# Amplifier.net
KiCad netlist of a schematic drawn in EAGLE
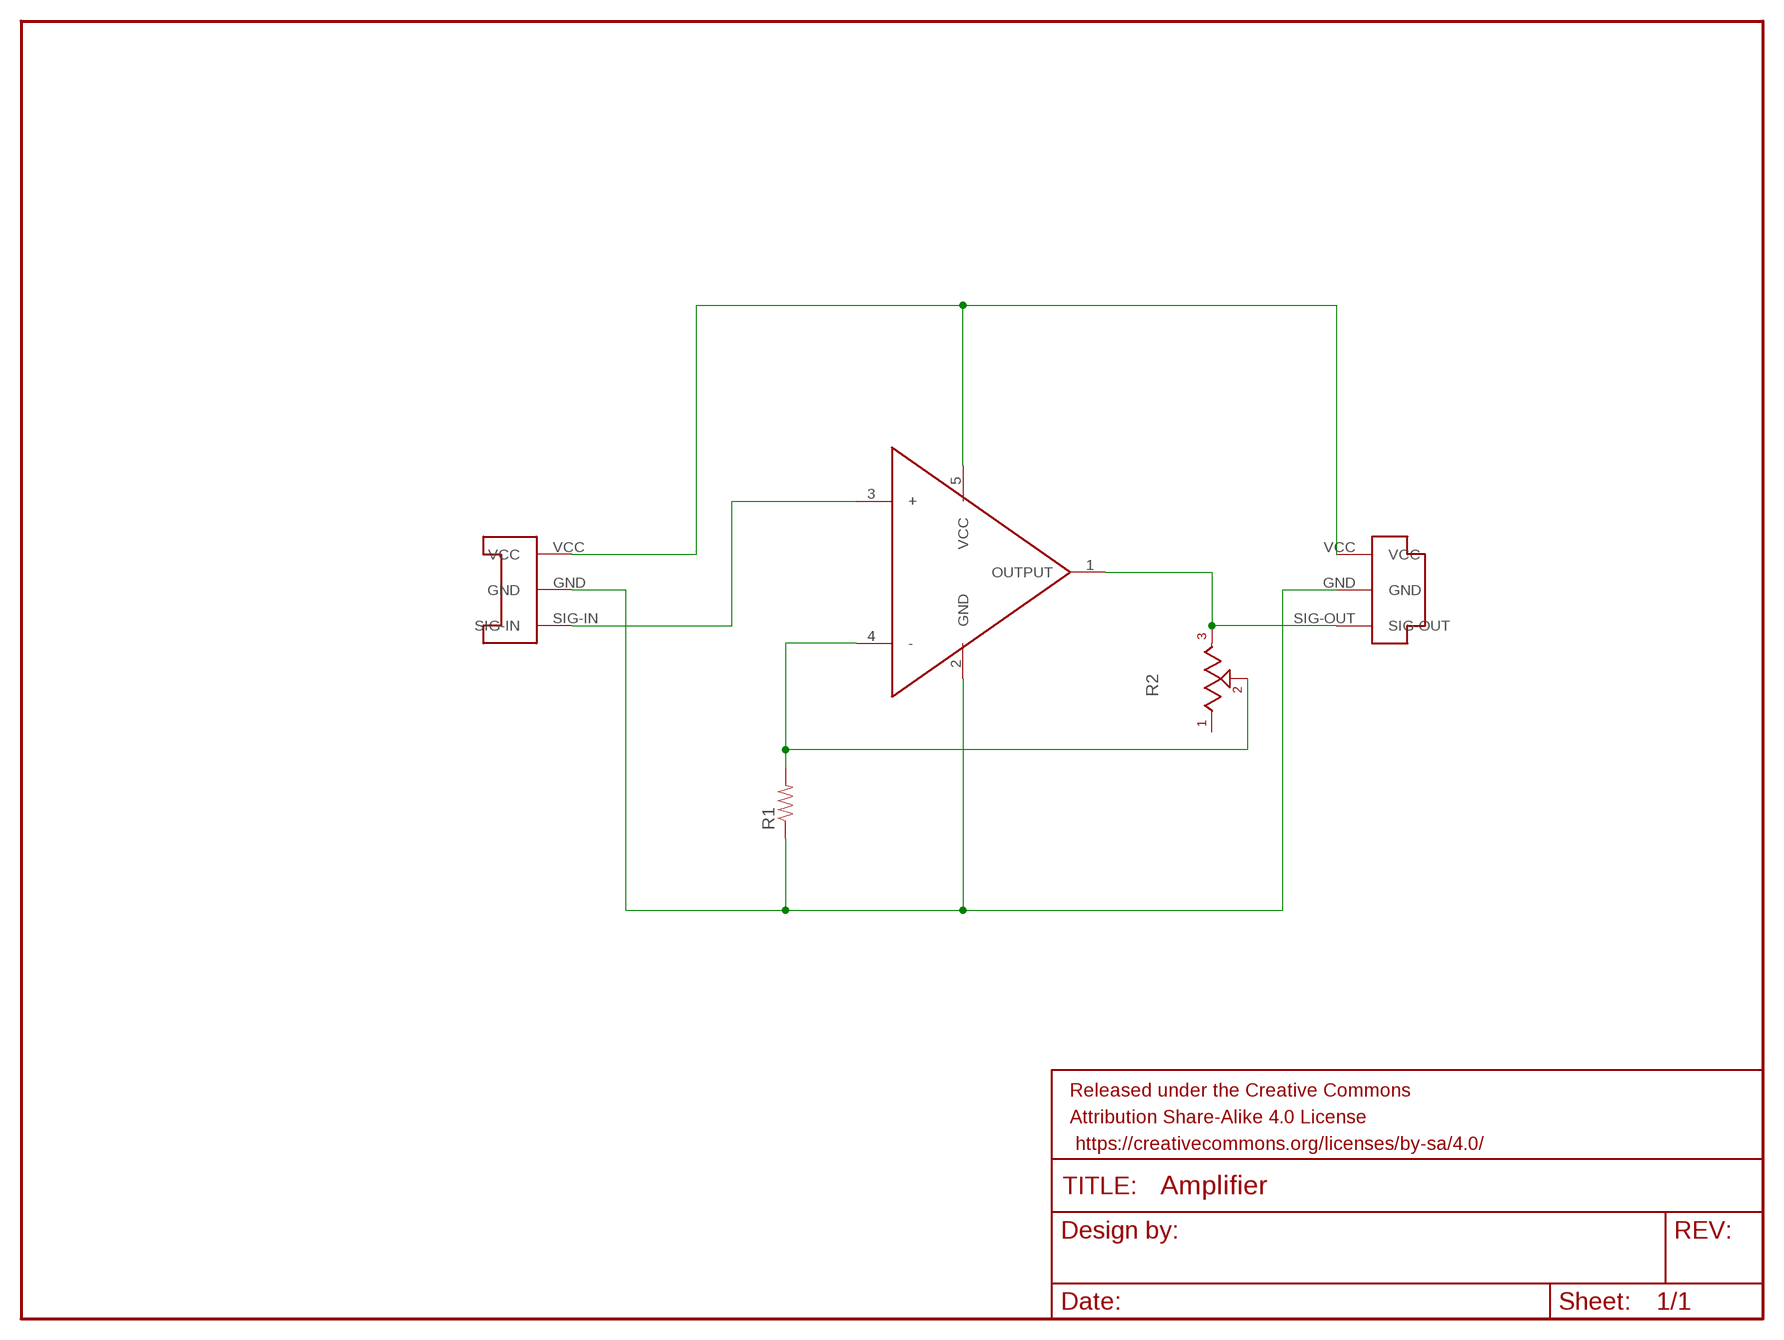
[diagram p0: schematic, sheet 1]

(export (version "E")
  (design (tool "Eeschema 10.0.6"))
  (components
    (comp (ref "FRAME1")
      (value "FRAME-LETTERNO_PACKAGE")
      (footprint "eagle-import:DUMMY")
      (fields (field (name "DESIGNER") "Nobody"))
      (libsource (lib "eagle-import") (part "FRAME-LETTERNO_PACKAGE"))
    )
    (comp (ref "R1")
      (value "RESISTOR0603")
      (footprint "eagle-import:0603-RES")
      (libsource (lib "eagle-import") (part "RESISTOR0603"))
    )
    (comp (ref "R2")
      (value "POT-TRIM-SMD-BOURNS-3314J-1")
      (footprint "eagle-import:POT-TRIM-SMD-BOURNS-3314")
      (libsource (lib "eagle-import") (part "POT-TRIM-SMD-BOURNS-3314J-1"))
    )
    (comp (ref "U$1")
      (value "CONN-PLUG-3POS-3MM")
      (footprint "eagle-import:PLUG-3POS-3MM-SMD")
      (libsource (lib "eagle-import") (part "CONN-PLUG-3POS-3MM"))
    )
    (comp (ref "U$2")
      (value "CONN-SOCKET-3POS-3MM")
      (footprint "eagle-import:SOCKET-3POS-3MM-SMD")
      (libsource (lib "eagle-import") (part "CONN-SOCKET-3POS-3MM"))
    )
    (comp (ref "U$3")
      (value "OPAMP-MCP6001SC70-5")
      (footprint "eagle-import:SC70")
      (libsource (lib "eagle-import") (part "OPAMP-MCP6001SC70-5"))
    )
  )
  (nets
    (net (code "1") (name "Net-(R2-3)") (class "Default")
      (node (ref "R2") (pin "1") (pinfunction "3_1") (pintype "passive"))
      (node (ref "U$1") (pin "SIG-OUT") (pinfunction "SIG-OUT_SIG-OUT") (pintype "bidirectional"))
      (node (ref "U$3") (pin "1") (pinfunction "OUTPUT_1") (pintype "output"))
    )
    (net (code "2") (name "Net-(U$3-+)") (class "Default")
      (node (ref "U$2") (pin "SIG-IN") (pinfunction "SIG-IN_SIG-IN") (pintype "bidirectional"))
      (node (ref "U$3") (pin "3") (pinfunction "+_3") (pintype "input"))
    )
    (net (code "3") (name "Net-(U$3--)") (class "Default")
      (node (ref "R1") (pin "2") (pinfunction "2_2") (pintype "passive"))
      (node (ref "R2") (pin "2") (pinfunction "2_2") (pintype "passive"))
      (node (ref "U$3") (pin "4") (pinfunction "-_4") (pintype "input"))
    )
    (net (code "4") (name "Net-(U$3-GND)") (class "Default")
      (node (ref "R1") (pin "1") (pinfunction "1_1") (pintype "passive"))
      (node (ref "U$1") (pin "GND") (pinfunction "GND_GND") (pintype "power_in"))
      (node (ref "U$2") (pin "GND") (pinfunction "GND_GND") (pintype "power_in"))
      (node (ref "U$3") (pin "2") (pinfunction "GND_2") (pintype "power_in"))
    )
    (net (code "5") (name "Net-(U$3-VCC)") (class "Default")
      (node (ref "U$1") (pin "VCC") (pinfunction "VCC_VCC") (pintype "power_in"))
      (node (ref "U$2") (pin "VCC") (pinfunction "VCC_VCC") (pintype "power_in"))
      (node (ref "U$3") (pin "5") (pinfunction "VCC_5") (pintype "power_in"))
    )
    (net (code "6") (name "unconnected-(R2-1-Pad3)") (class "Default")
      (node (ref "R2") (pin "3") (pinfunction "1_3") (pintype "passive"))
    )
  )
)
